# untitled.net
KiCad netlist of a schematic drawn in EAGLE
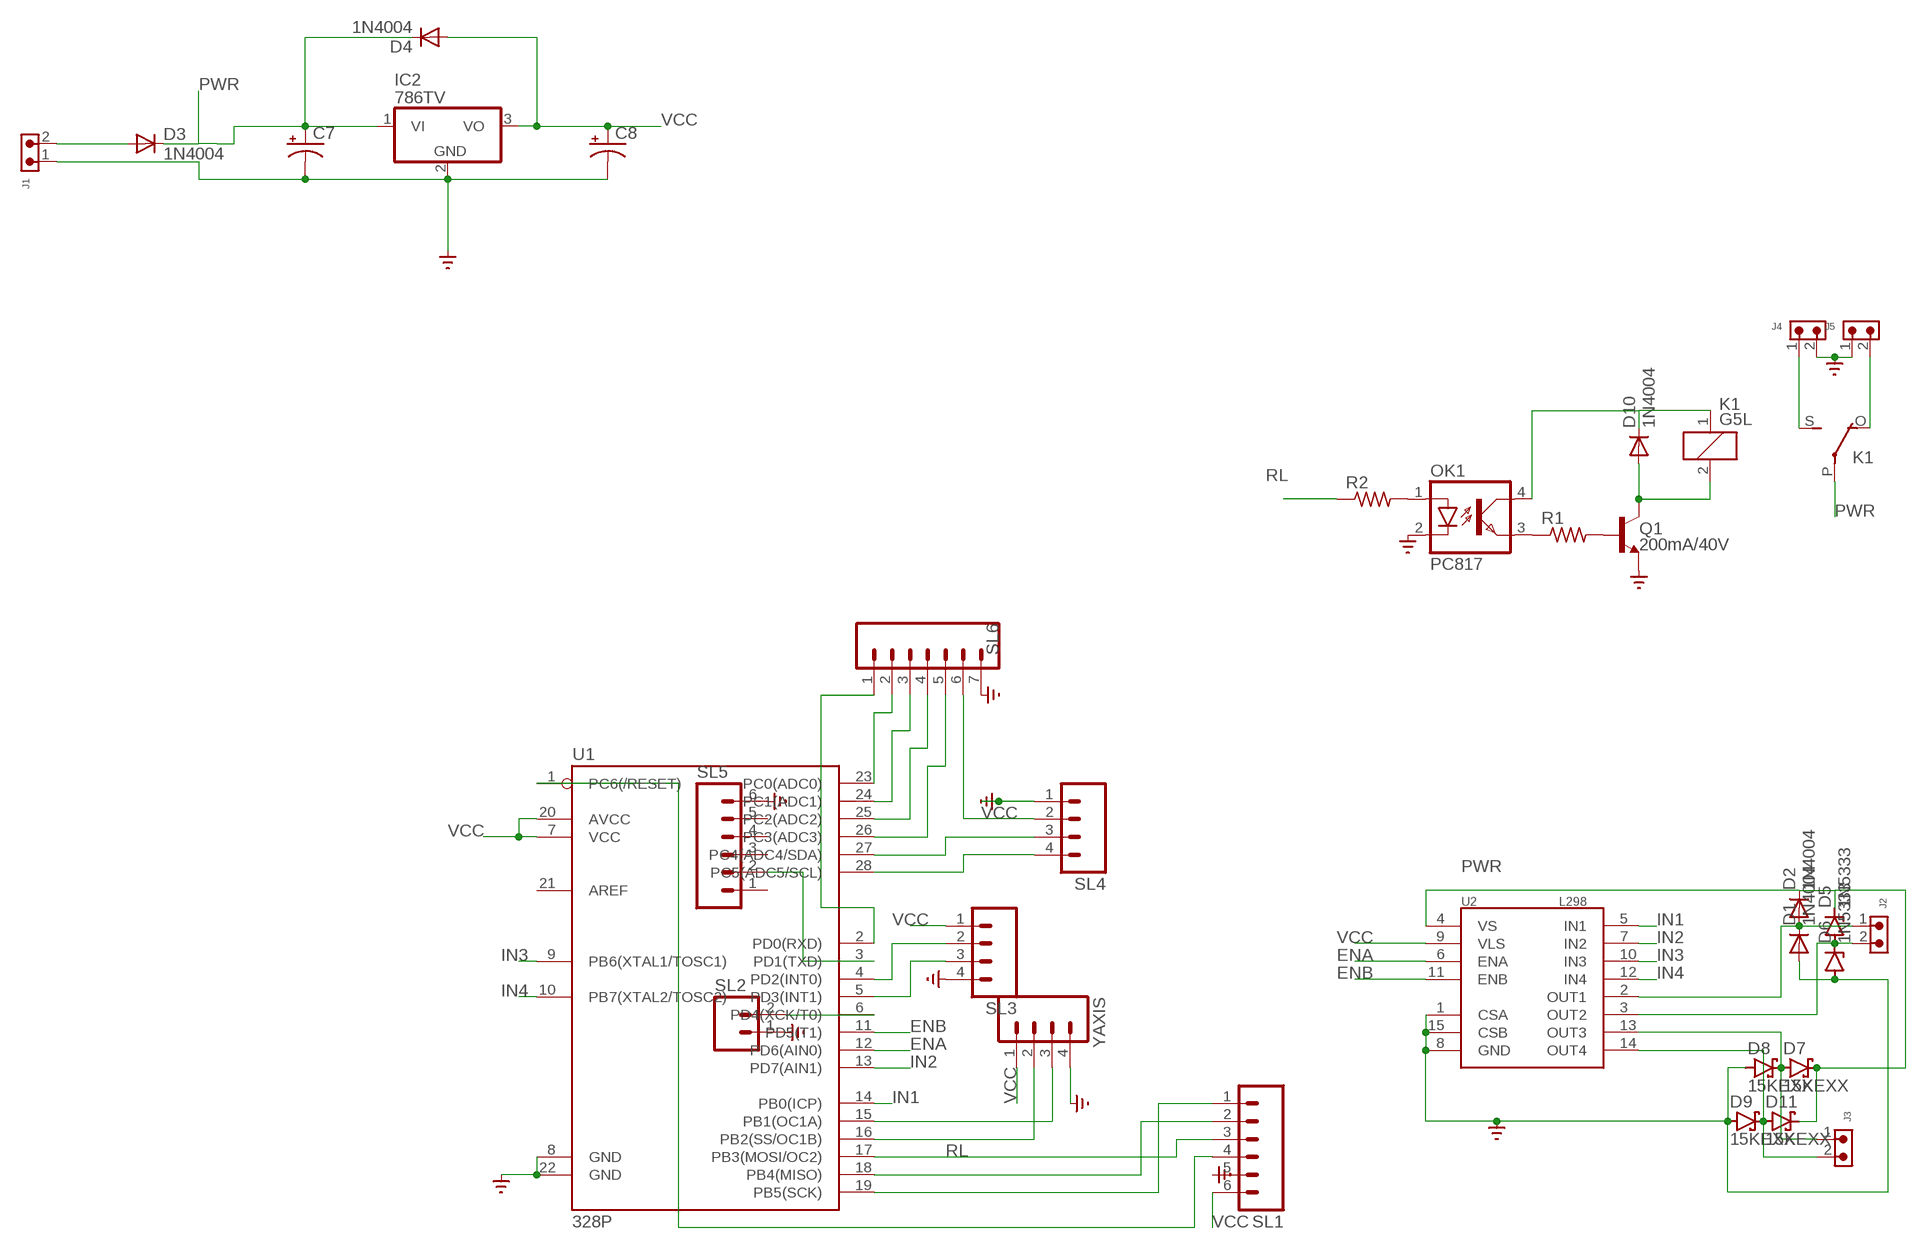
[diagram p0: schematic, sheet 1]

(export (version "E")
  (design (tool "Eeschema 10.0.6"))
  (components
    (comp (ref "C7")
      (value "CAPACITOR-PE5-10.5")
      (footprint "eagle-import:E5-10,5")
      (libsource (lib "eagle-import") (part "CAPACITOR-PE5-10.5"))
    )
    (comp (ref "C8")
      (value "CAPACITOR-PE5-6")
      (footprint "eagle-import:E5-6")
      (libsource (lib "eagle-import") (part "CAPACITOR-PE5-6"))
    )
    (comp (ref "D1")
      (value "1N4004")
      (footprint "eagle-import:DO41-10")
      (libsource (lib "eagle-import") (part "1N4004"))
    )
    (comp (ref "D2")
      (value "1N4004")
      (footprint "eagle-import:DO41-10")
      (libsource (lib "eagle-import") (part "1N4004"))
    )
    (comp (ref "D3")
      (value "1N4004")
      (footprint "eagle-import:DO41-10")
      (libsource (lib "eagle-import") (part "1N4004"))
    )
    (comp (ref "D4")
      (value "1N4004")
      (footprint "eagle-import:DO41-10")
      (libsource (lib "eagle-import") (part "1N4004"))
    )
    (comp (ref "D5")
      (value "1N5333")
      (footprint "eagle-import:C1702-15")
      (libsource (lib "eagle-import") (part "1N5333"))
    )
    (comp (ref "D6")
      (value "1N5333")
      (footprint "eagle-import:C1702-15")
      (libsource (lib "eagle-import") (part "1N5333"))
    )
    (comp (ref "D7")
      (value "15KEXX")
      (footprint "eagle-import:CB429-17")
      (libsource (lib "eagle-import") (part "15KEXX"))
    )
    (comp (ref "D8")
      (value "15KEXX")
      (footprint "eagle-import:CB429-17")
      (libsource (lib "eagle-import") (part "15KEXX"))
    )
    (comp (ref "D9")
      (value "15KEXX")
      (footprint "eagle-import:CB429-17")
      (libsource (lib "eagle-import") (part "15KEXX"))
    )
    (comp (ref "D10")
      (value "1N4004")
      (footprint "eagle-import:DO41-10")
      (libsource (lib "eagle-import") (part "1N4004"))
    )
    (comp (ref "D11")
      (value "15KEXX")
      (footprint "eagle-import:CB429-17")
      (libsource (lib "eagle-import") (part "15KEXX"))
    )
    (comp (ref "IC2")
      (value "786TV")
      (footprint "eagle-import:TO220V")
      (libsource (lib "eagle-import") (part "78TV6"))
    )
    (comp (ref "J1")
      (value "691305530002")
      (footprint "eagle-import:691305530002")
      (libsource (lib "eagle-import") (part "691305530002"))
    )
    (comp (ref "J2")
      (value "691305530002")
      (footprint "eagle-import:691305530002")
      (libsource (lib "eagle-import") (part "691305530002"))
    )
    (comp (ref "J3")
      (value "691305530002")
      (footprint "eagle-import:691305530002")
      (libsource (lib "eagle-import") (part "691305530002"))
    )
    (comp (ref "J4")
      (value "691305530002")
      (footprint "eagle-import:691305530002")
      (libsource (lib "eagle-import") (part "691305530002"))
    )
    (comp (ref "J5")
      (value "691305530002")
      (footprint "eagle-import:691305530002")
      (libsource (lib "eagle-import") (part "691305530002"))
    )
    (comp (ref "K1")
      (value "G5L")
      (footprint "eagle-import:G5LE")
      (libsource (lib "eagle-import") (part "G5L"))
    )
    (comp (ref "OK1")
      (value "PC817")
      (footprint "eagle-import:DIL04")
      (fields (field (name "MPN") "PC817X4J000F"))
      (libsource (lib "eagle-import") (part "PC817"))
    )
    (comp (ref "Q1")
      (value "200mA/40V")
      (footprint "eagle-import:TO-92")
      (libsource (lib "eagle-import") (part "TRANS_NPN-2N3904"))
    )
    (comp (ref "R1")
      (value "R-US_0207/10")
      (footprint "eagle-import:0207_10")
      (libsource (lib "eagle-import") (part "R-US_0207/10"))
    )
    (comp (ref "R2")
      (value "R-US_0207/10")
      (footprint "eagle-import:0207_10")
      (libsource (lib "eagle-import") (part "R-US_0207/10"))
    )
    (comp (ref "SL1")
      (value "M06")
      (footprint "eagle-import:06P")
      (libsource (lib "eagle-import") (part "M06"))
    )
    (comp (ref "SL2")
      (value "M02")
      (footprint "eagle-import:02P")
      (libsource (lib "eagle-import") (part "M02"))
    )
    (comp (ref "SL3")
      (value "M04")
      (footprint "eagle-import:04P")
      (libsource (lib "eagle-import") (part "M04"))
    )
    (comp (ref "SL4")
      (value "M04")
      (footprint "eagle-import:04P")
      (libsource (lib "eagle-import") (part "M04"))
    )
    (comp (ref "SL5")
      (value "M06")
      (footprint "eagle-import:06P")
      (libsource (lib "eagle-import") (part "M06"))
    )
    (comp (ref "SL6")
      (value "M07")
      (footprint "eagle-import:07P")
      (libsource (lib "eagle-import") (part "M07"))
    )
    (comp (ref "U1")
      (value "328P")
      (footprint "eagle-import:DIP28")
      (libsource (lib "eagle-import") (part "ATMEGA328P_PDIP"))
    )
    (comp (ref "U2")
      (value "L298")
      (footprint "eagle-import:MULTIWATT15")
      (libsource (lib "eagle-import") (part "L298"))
    )
    (comp (ref "YAXIS")
      (value "M04")
      (footprint "eagle-import:04P")
      (libsource (lib "eagle-import") (part "M04"))
    )
  )
  (nets
    (net (code "1") (name "/ENA") (class "Default")
      (node (ref "U1") (pin "12") (pinfunction "PD6(AIN0)_12") (pintype "bidirectional"))
      (node (ref "U2") (pin "6") (pinfunction "ENA_6") (pintype "bidirectional"))
    )
    (net (code "2") (name "/ENB") (class "Default")
      (node (ref "U1") (pin "11") (pinfunction "PD5(T1)_11") (pintype "bidirectional"))
      (node (ref "U2") (pin "11") (pinfunction "ENB_11") (pintype "bidirectional"))
    )
    (net (code "3") (name "/IN1") (class "Default")
      (node (ref "U1") (pin "14") (pinfunction "PB0(ICP)_14") (pintype "bidirectional"))
      (node (ref "U2") (pin "5") (pinfunction "IN1_5") (pintype "bidirectional"))
    )
    (net (code "4") (name "/IN2") (class "Default")
      (node (ref "U1") (pin "13") (pinfunction "PD7(AIN1)_13") (pintype "bidirectional"))
      (node (ref "U2") (pin "7") (pinfunction "IN2_7") (pintype "bidirectional"))
    )
    (net (code "5") (name "/IN3") (class "Default")
      (node (ref "U1") (pin "9") (pinfunction "PB6(XTAL1/TOSC1)_9") (pintype "bidirectional"))
      (node (ref "U2") (pin "10") (pinfunction "IN3_10") (pintype "bidirectional"))
    )
    (net (code "6") (name "/IN4") (class "Default")
      (node (ref "U1") (pin "10") (pinfunction "PB7(XTAL2/TOSC2)_10") (pintype "bidirectional"))
      (node (ref "U2") (pin "12") (pinfunction "IN4_12") (pintype "bidirectional"))
    )
    (net (code "7") (name "/PWR") (class "Default")
      (node (ref "C7") (pin "+") (pinfunction "+_+") (pintype "passive"))
      (node (ref "D11") (pin "C") (pinfunction "C_C") (pintype "passive"))
      (node (ref "D2") (pin "C") (pinfunction "C_C") (pintype "passive"))
      (node (ref "D3") (pin "A") (pinfunction "A_A") (pintype "passive"))
      (node (ref "D3") (pin "C") (pinfunction "C_C") (pintype "passive"))
      (node (ref "D4") (pin "C") (pinfunction "C_C") (pintype "passive"))
      (node (ref "D5") (pin "C") (pinfunction "C_C") (pintype "passive"))
      (node (ref "D7") (pin "C") (pinfunction "C_C") (pintype "passive"))
      (node (ref "IC2") (pin "1") (pinfunction "VI_1") (pintype "input"))
      (node (ref "J1") (pin "2") (pinfunction "2_2") (pintype "passive"))
      (node (ref "K1") (pin "P") (pinfunction "P_P") (pintype "passive"))
      (node (ref "U2") (pin "4") (pinfunction "VS_4") (pintype "bidirectional"))
    )
    (net (code "8") (name "/RL") (class "Default")
      (node (ref "R2") (pin "1") (pinfunction "1_1") (pintype "passive"))
      (node (ref "SL1") (pin "3") (pinfunction "3_3") (pintype "passive"))
      (node (ref "U1") (pin "17") (pinfunction "PB3(MOSI/OC2)_17") (pintype "bidirectional"))
    )
    (net (code "9") (name "/VCC") (class "Default")
      (node (ref "C8") (pin "+") (pinfunction "+_+") (pintype "passive"))
      (node (ref "D4") (pin "A") (pinfunction "A_A") (pintype "passive"))
      (node (ref "IC2") (pin "3") (pinfunction "VO_3") (pintype "passive"))
      (node (ref "SL1") (pin "6") (pinfunction "6_6") (pintype "passive"))
      (node (ref "SL3") (pin "1") (pinfunction "1_1") (pintype "passive"))
      (node (ref "SL4") (pin "2") (pinfunction "2_2") (pintype "passive"))
      (node (ref "SL6") (pin "6") (pinfunction "6_6") (pintype "passive"))
      (node (ref "U1") (pin "20") (pinfunction "AVCC_20") (pintype "bidirectional"))
      (node (ref "U1") (pin "7") (pinfunction "VCC_7") (pintype "bidirectional"))
      (node (ref "U2") (pin "9") (pinfunction "VLS_9") (pintype "bidirectional"))
      (node (ref "YAXIS") (pin "1") (pinfunction "1_1") (pintype "passive"))
    )
    (net (code "10") (name "Net-(J4-Pad1)") (class "Default")
      (node (ref "J4") (pin "1") (pinfunction "1_1") (pintype "passive"))
      (node (ref "K1") (pin "S") (pinfunction "S_S") (pintype "passive"))
    )
    (net (code "11") (name "Net-(J5-Pad2)") (class "Default")
      (node (ref "J5") (pin "2") (pinfunction "2_2") (pintype "passive"))
      (node (ref "K1") (pin "O") (pinfunction "O_O") (pintype "passive"))
    )
    (net (code "12") (name "Net-(OK1-A)") (class "Default")
      (node (ref "OK1") (pin "1") (pinfunction "A_1") (pintype "passive"))
      (node (ref "R2") (pin "2") (pinfunction "2_2") (pintype "passive"))
    )
    (net (code "13") (name "Net-(OK1-COL)") (class "Default")
      (node (ref "D10") (pin "C") (pinfunction "C_C") (pintype "passive"))
      (node (ref "K1") (pin "1") (pinfunction "1_1") (pintype "passive"))
      (node (ref "OK1") (pin "4") (pinfunction "COL_4") (pintype "passive"))
    )
    (net (code "14") (name "Net-(OK1-EMIT)") (class "Default")
      (node (ref "OK1") (pin "3") (pinfunction "EMIT_3") (pintype "passive"))
      (node (ref "R1") (pin "1") (pinfunction "1_1") (pintype "passive"))
    )
    (net (code "15") (name "Net-(Q1-B)") (class "Default")
      (node (ref "Q1") (pin "2") (pinfunction "B_2") (pintype "passive"))
      (node (ref "R1") (pin "2") (pinfunction "2_2") (pintype "passive"))
    )
    (net (code "16") (name "Net-(Q1-C)") (class "Default")
      (node (ref "D10") (pin "A") (pinfunction "A_A") (pintype "passive"))
      (node (ref "K1") (pin "2") (pinfunction "2_2") (pintype "passive"))
      (node (ref "Q1") (pin "3") (pinfunction "C_3") (pintype "passive"))
    )
    (net (code "17") (name "Net-(U1-PB1(OC1A))") (class "Default")
      (node (ref "U1") (pin "15") (pinfunction "PB1(OC1A)_15") (pintype "bidirectional"))
      (node (ref "YAXIS") (pin "3") (pinfunction "3_3") (pintype "passive"))
    )
    (net (code "18") (name "Net-(U1-PB2(SS{slash}OC1B))") (class "Default")
      (node (ref "U1") (pin "16") (pinfunction "PB2(SS/OC1B)_16") (pintype "bidirectional"))
      (node (ref "YAXIS") (pin "2") (pinfunction "2_2") (pintype "passive"))
    )
    (net (code "19") (name "Net-(U1-PB4(MISO))") (class "Default")
      (node (ref "SL1") (pin "2") (pinfunction "2_2") (pintype "passive"))
      (node (ref "U1") (pin "18") (pinfunction "PB4(MISO)_18") (pintype "bidirectional"))
    )
    (net (code "20") (name "Net-(U1-PB5(SCK))") (class "Default")
      (node (ref "SL1") (pin "1") (pinfunction "1_1") (pintype "passive"))
      (node (ref "U1") (pin "19") (pinfunction "PB5(SCK)_19") (pintype "bidirectional"))
    )
    (net (code "21") (name "Net-(U1-PC0(ADC0))") (class "Default")
      (node (ref "SL6") (pin "2") (pinfunction "2_2") (pintype "passive"))
      (node (ref "U1") (pin "23") (pinfunction "PC0(ADC0)_23") (pintype "bidirectional"))
    )
    (net (code "22") (name "Net-(U1-PC1(ADC1))") (class "Default")
      (node (ref "SL6") (pin "3") (pinfunction "3_3") (pintype "passive"))
      (node (ref "U1") (pin "24") (pinfunction "PC1(ADC1)_24") (pintype "bidirectional"))
    )
    (net (code "23") (name "Net-(U1-PC2(ADC2))") (class "Default")
      (node (ref "SL6") (pin "4") (pinfunction "4_4") (pintype "passive"))
      (node (ref "U1") (pin "25") (pinfunction "PC2(ADC2)_25") (pintype "bidirectional"))
    )
    (net (code "24") (name "Net-(U1-PC3(ADC3))") (class "Default")
      (node (ref "SL6") (pin "5") (pinfunction "5_5") (pintype "passive"))
      (node (ref "U1") (pin "26") (pinfunction "PC3(ADC3)_26") (pintype "bidirectional"))
    )
    (net (code "25") (name "Net-(U1-PC4(ADC4{slash}SDA))") (class "Default")
      (node (ref "SL4") (pin "3") (pinfunction "3_3") (pintype "passive"))
      (node (ref "U1") (pin "27") (pinfunction "PC4(ADC4/SDA)_27") (pintype "bidirectional"))
    )
    (net (code "26") (name "Net-(U1-PC5(ADC5{slash}SCL))") (class "Default")
      (node (ref "SL4") (pin "4") (pinfunction "4_4") (pintype "passive"))
      (node (ref "U1") (pin "28") (pinfunction "PC5(ADC5/SCL)_28") (pintype "bidirectional"))
    )
    (net (code "27") (name "Net-(U1-PC6({slash}RESET))") (class "Default")
      (node (ref "SL1") (pin "4") (pinfunction "4_4") (pintype "passive"))
      (node (ref "U1") (pin "1") (pinfunction "PC6(/RESET)_1") (pintype "bidirectional"))
    )
    (net (code "28") (name "Net-(U1-PD0(RXD))") (class "Default")
      (node (ref "SL6") (pin "1") (pinfunction "1_1") (pintype "passive"))
      (node (ref "U1") (pin "2") (pinfunction "PD0(RXD)_2") (pintype "bidirectional"))
    )
    (net (code "29") (name "Net-(U1-PD1(TXD))") (class "Default")
      (node (ref "SL5") (pin "2") (pinfunction "2_2") (pintype "passive"))
      (node (ref "U1") (pin "3") (pinfunction "PD1(TXD)_3") (pintype "bidirectional"))
    )
    (net (code "30") (name "Net-(U1-PD2(INT0))") (class "Default")
      (node (ref "SL3") (pin "2") (pinfunction "2_2") (pintype "passive"))
      (node (ref "U1") (pin "4") (pinfunction "PD2(INT0)_4") (pintype "bidirectional"))
    )
    (net (code "31") (name "Net-(U1-PD3(INT1))") (class "Default")
      (node (ref "SL3") (pin "3") (pinfunction "3_3") (pintype "passive"))
      (node (ref "U1") (pin "5") (pinfunction "PD3(INT1)_5") (pintype "bidirectional"))
    )
    (net (code "32") (name "Net-(U1-PD4(XCK{slash}T0))") (class "Default")
      (node (ref "SL2") (pin "2") (pinfunction "2_2") (pintype "passive"))
      (node (ref "U1") (pin "6") (pinfunction "PD4(XCK/T0)_6") (pintype "bidirectional"))
    )
    (net (code "33") (name "Net-(U2-OUT1)") (class "Default")
      (node (ref "D1") (pin "C") (pinfunction "C_C") (pintype "passive"))
      (node (ref "D2") (pin "A") (pinfunction "A_A") (pintype "passive"))
      (node (ref "J2") (pin "1") (pinfunction "1_1") (pintype "passive"))
      (node (ref "U2") (pin "2") (pinfunction "OUT1_2") (pintype "bidirectional"))
    )
    (net (code "34") (name "Net-(U2-OUT2)") (class "Default")
      (node (ref "D5") (pin "A") (pinfunction "A_A") (pintype "passive"))
      (node (ref "D6") (pin "C") (pinfunction "C_C") (pintype "passive"))
      (node (ref "J2") (pin "2") (pinfunction "2_2") (pintype "passive"))
      (node (ref "U2") (pin "3") (pinfunction "OUT2_3") (pintype "bidirectional"))
    )
    (net (code "35") (name "Net-(U2-OUT3)") (class "Default")
      (node (ref "D7") (pin "A") (pinfunction "A_A") (pintype "passive"))
      (node (ref "D8") (pin "C") (pinfunction "C_C") (pintype "passive"))
      (node (ref "J3") (pin "1") (pinfunction "1_1") (pintype "passive"))
      (node (ref "U2") (pin "13") (pinfunction "OUT3_13") (pintype "bidirectional"))
    )
    (net (code "36") (name "Net-(U2-OUT4)") (class "Default")
      (node (ref "D11") (pin "A") (pinfunction "A_A") (pintype "passive"))
      (node (ref "D9") (pin "C") (pinfunction "C_C") (pintype "passive"))
      (node (ref "J3") (pin "2") (pinfunction "2_2") (pintype "passive"))
      (node (ref "U2") (pin "14") (pinfunction "OUT4_14") (pintype "bidirectional"))
    )
    (net (code "37") (name "SUPPLY_BRASTAN_GND_") (class "Default")
      (node (ref "C7") (pin "-") (pinfunction "-_-") (pintype "passive"))
      (node (ref "C8") (pin "-") (pinfunction "-_-") (pintype "passive"))
      (node (ref "D1") (pin "A") (pinfunction "A_A") (pintype "passive"))
      (node (ref "D6") (pin "A") (pinfunction "A_A") (pintype "passive"))
      (node (ref "D8") (pin "A") (pinfunction "A_A") (pintype "passive"))
      (node (ref "D9") (pin "A") (pinfunction "A_A") (pintype "passive"))
      (node (ref "IC2") (pin "2") (pinfunction "GND_2") (pintype "passive"))
      (node (ref "J1") (pin "1") (pinfunction "1_1") (pintype "passive"))
      (node (ref "J4") (pin "2") (pinfunction "2_2") (pintype "passive"))
      (node (ref "J5") (pin "1") (pinfunction "1_1") (pintype "passive"))
      (node (ref "OK1") (pin "2") (pinfunction "C_2") (pintype "passive"))
      (node (ref "Q1") (pin "1") (pinfunction "E_1") (pintype "passive"))
      (node (ref "SL1") (pin "5") (pinfunction "5_5") (pintype "passive"))
      (node (ref "SL2") (pin "1") (pinfunction "1_1") (pintype "passive"))
      (node (ref "SL3") (pin "4") (pinfunction "4_4") (pintype "passive"))
      (node (ref "SL4") (pin "1") (pinfunction "1_1") (pintype "passive"))
      (node (ref "SL5") (pin "6") (pinfunction "6_6") (pintype "passive"))
      (node (ref "SL6") (pin "7") (pinfunction "7_7") (pintype "passive"))
      (node (ref "U1") (pin "22") (pinfunction "GND_22") (pintype "bidirectional"))
      (node (ref "U1") (pin "8") (pinfunction "GND_8") (pintype "bidirectional"))
      (node (ref "U2") (pin "1") (pinfunction "CSA_1") (pintype "bidirectional"))
      (node (ref "U2") (pin "15") (pinfunction "CSB_15") (pintype "bidirectional"))
      (node (ref "U2") (pin "8") (pinfunction "GND_8") (pintype "bidirectional"))
      (node (ref "YAXIS") (pin "4") (pinfunction "4_4") (pintype "passive"))
    )
    (net (code "38") (name "unconnected-(SL5-Pad1)") (class "Default")
      (node (ref "SL5") (pin "1") (pinfunction "1_1") (pintype "passive"))
    )
    (net (code "39") (name "unconnected-(SL5-Pad3)") (class "Default")
      (node (ref "SL5") (pin "3") (pinfunction "3_3") (pintype "passive"))
    )
    (net (code "40") (name "unconnected-(SL5-Pad4)") (class "Default")
      (node (ref "SL5") (pin "4") (pinfunction "4_4") (pintype "passive"))
    )
    (net (code "41") (name "unconnected-(SL5-Pad5)") (class "Default")
      (node (ref "SL5") (pin "5") (pinfunction "5_5") (pintype "passive"))
    )
    (net (code "42") (name "unconnected-(U1-AREF-Pad21)") (class "Default")
      (node (ref "U1") (pin "21") (pinfunction "AREF_21") (pintype "bidirectional"))
    )
  )
)
